# mainboard_valdis.net
KiCad netlist of a schematic drawn in Altium Designer
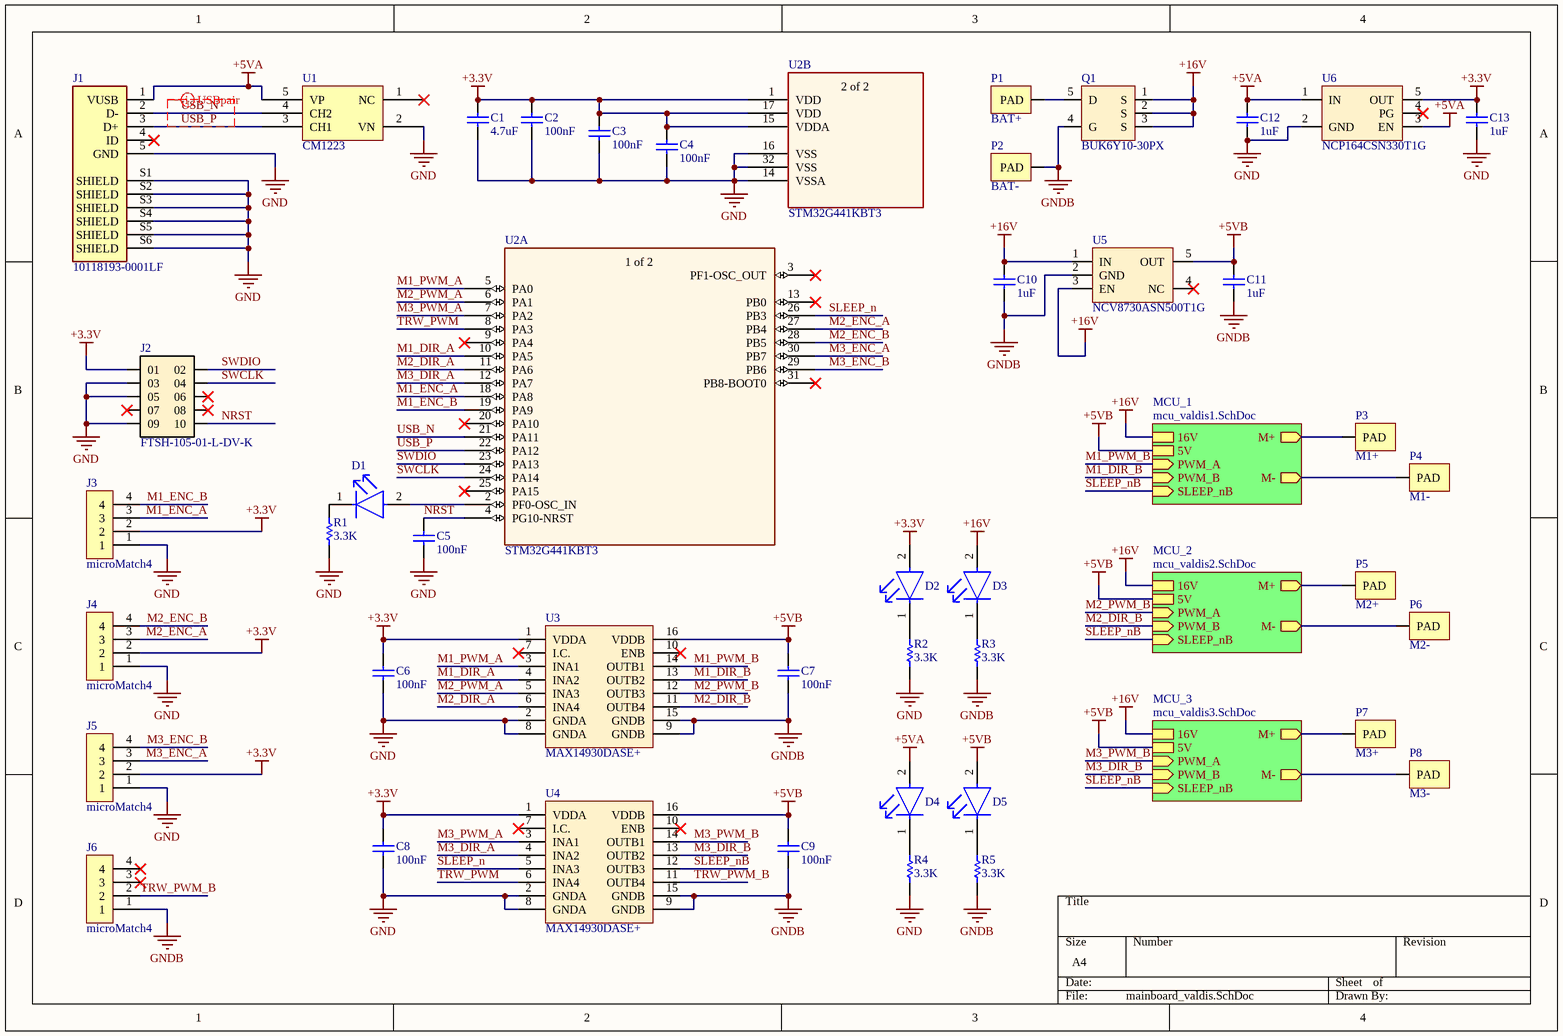
[diagram p0: mainboard_valdis.SchDoc]

(export (version "E")
  (design (tool "Eeschema 10.0.6"))
  (components
    (comp (ref "C1")
      (value "4.7uF")
      (footprint "CAPC1608X90X35ML10T15")
      (description "Chip Capacitor, 22 pF, +/- 5%, 50 V, -55 to 125 degC, 0603 (1608 Metric), RoHS, Tape and Reel")
      (fields (field (name "MANUFACTURER") "Murata"))
      (libsource (lib "Altium Content Vault") (part "CAP-NP-2"))
    )
    (comp (ref "C2")
      (value "100nF")
      (footprint "CAPC1608X90X35ML10T15")
      (description "Chip Capacitor, 22 pF, +/- 5%, 50 V, -55 to 125 degC, 0603 (1608 Metric), RoHS, Tape and Reel")
      (fields (field (name "MANUFACTURER") "Murata"))
      (libsource (lib "Altium Content Vault") (part "CAP-NP-2"))
    )
    (comp (ref "C3")
      (value "100nF")
      (footprint "CAPC1608X90X35ML10T15")
      (description "Chip Capacitor, 22 pF, +/- 5%, 50 V, -55 to 125 degC, 0603 (1608 Metric), RoHS, Tape and Reel")
      (fields (field (name "MANUFACTURER") "Murata"))
      (libsource (lib "Altium Content Vault") (part "CAP-NP-2"))
    )
    (comp (ref "C4")
      (value "100nF")
      (footprint "CAPC1608X90X35ML10T15")
      (description "Chip Capacitor, 22 pF, +/- 5%, 50 V, -55 to 125 degC, 0603 (1608 Metric), RoHS, Tape and Reel")
      (fields (field (name "MANUFACTURER") "Murata"))
      (libsource (lib "Altium Content Vault") (part "CAP-NP-2"))
    )
    (comp (ref "C5")
      (value "100nF")
      (footprint "CAPC1608X90X35ML10T15")
      (description "Chip Capacitor, 22 pF, +/- 5%, 50 V, -55 to 125 degC, 0603 (1608 Metric), RoHS, Tape and Reel")
      (fields (field (name "MANUFACTURER") "Murata"))
      (libsource (lib "Altium Content Vault") (part "CAP-NP-2"))
    )
    (comp (ref "C6")
      (value "100nF")
      (footprint "CAPC1608X90X35ML10T15")
      (description "Chip Capacitor, 22 pF, +/- 5%, 50 V, -55 to 125 degC, 0603 (1608 Metric), RoHS, Tape and Reel")
      (fields (field (name "MANUFACTURER") "Murata"))
      (libsource (lib "Altium Content Vault") (part "CAP-NP-2"))
    )
    (comp (ref "C7")
      (value "100nF")
      (footprint "CAPC1608X90X35ML10T15")
      (description "Chip Capacitor, 22 pF, +/- 5%, 50 V, -55 to 125 degC, 0603 (1608 Metric), RoHS, Tape and Reel")
      (fields (field (name "MANUFACTURER") "Murata"))
      (libsource (lib "Altium Content Vault") (part "CAP-NP-2"))
    )
    (comp (ref "C8")
      (value "100nF")
      (footprint "CAPC1608X90X35ML10T15")
      (description "Chip Capacitor, 22 pF, +/- 5%, 50 V, -55 to 125 degC, 0603 (1608 Metric), RoHS, Tape and Reel")
      (fields (field (name "MANUFACTURER") "Murata"))
      (libsource (lib "Altium Content Vault") (part "CAP-NP-2"))
    )
    (comp (ref "C9")
      (value "100nF")
      (footprint "CAPC1608X90X35ML10T15")
      (description "Chip Capacitor, 22 pF, +/- 5%, 50 V, -55 to 125 degC, 0603 (1608 Metric), RoHS, Tape and Reel")
      (fields (field (name "MANUFACTURER") "Murata"))
      (libsource (lib "Altium Content Vault") (part "CAP-NP-2"))
    )
    (comp (ref "C10")
      (value "1uF")
      (footprint "CAPC1608X90X35ML10T15")
      (description "Chip Capacitor, 22 pF, +/- 5%, 50 V, -55 to 125 degC, 0603 (1608 Metric), RoHS, Tape and Reel")
      (fields (field (name "MANUFACTURER") "Murata"))
      (libsource (lib "Altium Content Vault") (part "CAP-NP-2"))
    )
    (comp (ref "C11")
      (value "1uF")
      (footprint "CAPC1608X90X35ML10T15")
      (description "Chip Capacitor, 22 pF, +/- 5%, 50 V, -55 to 125 degC, 0603 (1608 Metric), RoHS, Tape and Reel")
      (fields (field (name "MANUFACTURER") "Murata"))
      (libsource (lib "Altium Content Vault") (part "CAP-NP-2"))
    )
    (comp (ref "C12")
      (value "1uF")
      (footprint "CAPC1608X90X35ML10T15")
      (description "Chip Capacitor, 22 pF, +/- 5%, 50 V, -55 to 125 degC, 0603 (1608 Metric), RoHS, Tape and Reel")
      (fields (field (name "MANUFACTURER") "Murata"))
      (libsource (lib "Altium Content Vault") (part "CAP-NP-2"))
    )
    (comp (ref "C13")
      (value "1uF")
      (footprint "CAPC1608X90X35ML10T15")
      (description "Chip Capacitor, 22 pF, +/- 5%, 50 V, -55 to 125 degC, 0603 (1608 Metric), RoHS, Tape and Reel")
      (fields (field (name "MANUFACTURER") "Murata"))
      (libsource (lib "Altium Content Vault") (part "CAP-NP-2"))
    )
    (comp (ref "D1")
      (value "LTST-C191TBKT")
      (footprint "FP-LTST-C191TBKT-MFG")
      (description "LED BLUE CLEAR CHIP SMD")
      (libsource (lib "Altium Content Vault") (part "8706943c75ba83719d021d2fdc84c58"))
    )
    (comp (ref "D2")
      (value "LTST-C191TBKT")
      (footprint "FP-LTST-C191TBKT-MFG")
      (description "LED BLUE CLEAR CHIP SMD")
      (libsource (lib "Altium Content Vault") (part "8706943c75ba83719d021d2fdc84c58"))
    )
    (comp (ref "D3")
      (value "LTST-C191TBKT")
      (footprint "FP-LTST-C191TBKT-MFG")
      (description "LED BLUE CLEAR CHIP SMD")
      (libsource (lib "Altium Content Vault") (part "8706943c75ba83719d021d2fdc84c58"))
    )
    (comp (ref "D4")
      (value "LTST-C191TBKT")
      (footprint "FP-LTST-C191TBKT-MFG")
      (description "LED BLUE CLEAR CHIP SMD")
      (libsource (lib "Altium Content Vault") (part "8706943c75ba83719d021d2fdc84c58"))
    )
    (comp (ref "D5")
      (value "LTST-C191TBKT")
      (footprint "FP-LTST-C191TBKT-MFG")
      (description "LED BLUE CLEAR CHIP SMD")
      (libsource (lib "Altium Content Vault") (part "8706943c75ba83719d021d2fdc84c58"))
    )
    (comp (ref "J1")
      (value "10118193-0001LF")
      (footprint "FCI_10118193-0001LF")
      (description "USB - micro B USB 2.0 Receptacle Connector 5 Position Surface Mount, Right Angle; Through Hole")
      (fields (field (name "MF") "Amphenol ICC"))
      (libsource (lib "Valdis_Components") (part "10118193-0001LF"))
    )
    (comp (ref "J2")
      (value "FTSH-105-01-L-DV-K")
      (footprint "FTSH-105-01-XXX-DV-K")
      (libsource (lib "Valdis_Components") (part "FTSH-105-01-L-DV-K"))
    )
    (comp (ref "J3")
      (value "microMatch4")
      (footprint "microMatch4:microMatch4")
      (libsource (lib "Valdis_Components") (part "microMatch4"))
    )
    (comp (ref "J4")
      (value "microMatch4")
      (footprint "microMatch4:microMatch4")
      (libsource (lib "Valdis_Components") (part "microMatch4"))
    )
    (comp (ref "J5")
      (value "microMatch4")
      (footprint "microMatch4:microMatch4")
      (libsource (lib "Valdis_Components") (part "microMatch4"))
    )
    (comp (ref "J6")
      (value "microMatch4")
      (footprint "microMatch4:microMatch4")
      (libsource (lib "Valdis_Components") (part "microMatch4"))
    )
    (comp (ref "P1") (value "BAT+") (footprint "PCBComponent_1") (libsource (lib "") (part "Pad4x4_1")))
    (comp (ref "P2") (value "BAT-") (footprint "PCBComponent_1") (libsource (lib "") (part "Pad4x4_1")))
    (comp (ref "P3")
      (value "M1+")
      (footprint "PCBComponent_1")
      (libsource (lib "Valdis_Components") (part "Pad4x4"))
    )
    (comp (ref "P4")
      (value "M1-")
      (footprint "PCBComponent_1")
      (libsource (lib "Valdis_Components") (part "Pad4x4"))
    )
    (comp (ref "P5")
      (value "M2+")
      (footprint "PCBComponent_1")
      (libsource (lib "Valdis_Components") (part "Pad4x4"))
    )
    (comp (ref "P6")
      (value "M2-")
      (footprint "PCBComponent_1")
      (libsource (lib "Valdis_Components") (part "Pad4x4"))
    )
    (comp (ref "P7")
      (value "M3+")
      (footprint "PCBComponent_1")
      (libsource (lib "Valdis_Components") (part "Pad4x4"))
    )
    (comp (ref "P8")
      (value "M3-")
      (footprint "PCBComponent_1")
      (libsource (lib "Valdis_Components") (part "Pad4x4"))
    )
    (comp (ref "Q1")
      (value "BUK6Y10-30PX")
      (footprint "TO127P600X120-5N")
      (libsource (lib "Valdis_Components") (part "BUK6Y10-30PX"))
    )
    (comp (ref "R1")
      (value "3.3K")
      (footprint "RESC1609X50X30NL8T20")
      (description "Chip Resistor, 0 Ohm, Jumper, 100 mW, -55 to 155 degC, 0603 (1608 Metric), RoHS, Tape and Reel")
      (fields (field (name "MANUFACTURER") "Vishay Semiconductor"))
      (libsource (lib "Altium Content Vault") (part "RES-2"))
    )
    (comp (ref "R2")
      (value "3.3K")
      (footprint "RESC1609X50X30NL8T20")
      (description "Chip Resistor, 0 Ohm, Jumper, 100 mW, -55 to 155 degC, 0603 (1608 Metric), RoHS, Tape and Reel")
      (fields (field (name "MANUFACTURER") "Vishay Semiconductor"))
      (libsource (lib "Altium Content Vault") (part "RES-2"))
    )
    (comp (ref "R3")
      (value "3.3K")
      (footprint "RESC1609X50X30NL8T20")
      (description "Chip Resistor, 0 Ohm, Jumper, 100 mW, -55 to 155 degC, 0603 (1608 Metric), RoHS, Tape and Reel")
      (fields (field (name "MANUFACTURER") "Vishay Semiconductor"))
      (libsource (lib "Altium Content Vault") (part "RES-2"))
    )
    (comp (ref "R4")
      (value "3.3K")
      (footprint "RESC1609X50X30NL8T20")
      (description "Chip Resistor, 0 Ohm, Jumper, 100 mW, -55 to 155 degC, 0603 (1608 Metric), RoHS, Tape and Reel")
      (fields (field (name "MANUFACTURER") "Vishay Semiconductor"))
      (libsource (lib "Altium Content Vault") (part "RES-2"))
    )
    (comp (ref "R5")
      (value "3.3K")
      (footprint "RESC1609X50X30NL8T20")
      (description "Chip Resistor, 0 Ohm, Jumper, 100 mW, -55 to 155 degC, 0603 (1608 Metric), RoHS, Tape and Reel")
      (fields (field (name "MANUFACTURER") "Vishay Semiconductor"))
      (libsource (lib "Altium Content Vault") (part "RES-2"))
    )
    (comp (ref "U1")
      (value "CM1223")
      (footprint "SOT23-5")
      (libsource (lib "Valdis_Components") (part "CM1223"))
    )
    (comp (ref "U2")
      (value "STM32G441KBT3")
      (footprint "LQFP32_7X7_STM")
      (description "No Description Available")
      (fields (field (name "COPYRIGHT") "Copyright (C) 2018 Accelerated Designs. All rights reserved"))
      (libsource (lib "Valdis_Components") (part "STM32G441KBT3"))
    )
    (comp (ref "U3")
      (value "MAX14930DASE+")
      (footprint "21-0041_S16+1_MXM")
      (libsource (lib "Valdis_Components") (part "MAX14930DASE+"))
    )
    (comp (ref "U4")
      (value "MAX14930DASE+")
      (footprint "21-0041_S16+1_MXM")
      (libsource (lib "Valdis_Components") (part "MAX14930DASE+"))
    )
    (comp (ref "U5")
      (value "NCV8730ASN500T1G")
      (footprint "NCV8730:TSSOP5")
      (libsource (lib "NCV8730ASN500T1G") (part "NCV8730ASN500T1G"))
    )
    (comp (ref "U6")
      (value "NCP164CSN330T1G")
      (footprint "SOP95P275X110-5N")
      (libsource (lib "Valdis_Components") (part "NCP164CSN330T1G"))
    )
  )
  (nets
    (net (code "1") (name "+3.3V") (class "Default")
      (node (ref "C1") (pin "2") (pinfunction "2_2") (pintype "passive"))
      (node (ref "C13") (pin "2") (pinfunction "2_2") (pintype "passive"))
      (node (ref "C2") (pin "2") (pinfunction "2_2") (pintype "passive"))
      (node (ref "C3") (pin "2") (pinfunction "2_2") (pintype "passive"))
      (node (ref "C4") (pin "2") (pinfunction "2_2") (pintype "passive"))
      (node (ref "C6") (pin "2") (pinfunction "2_2") (pintype "passive"))
      (node (ref "C8") (pin "2") (pinfunction "2_2") (pintype "passive"))
      (node (ref "D2") (pin "2") (pinfunction "A_2") (pintype "passive"))
      (node (ref "J2") (pin "1") (pinfunction "01_1") (pintype "passive"))
      (node (ref "J3") (pin "2") (pinfunction "2_2") (pintype "passive"))
      (node (ref "J4") (pin "2") (pinfunction "2_2") (pintype "passive"))
      (node (ref "J5") (pin "2") (pinfunction "2_2") (pintype "passive"))
      (node (ref "U2") (pin "1") (pinfunction "VDD_1") (pintype "power_in"))
      (node (ref "U2") (pin "15") (pinfunction "VDDA_15") (pintype "power_in"))
      (node (ref "U2") (pin "17") (pinfunction "VDD_17") (pintype "power_in"))
      (node (ref "U3") (pin "1") (pinfunction "VDDA_1") (pintype "passive"))
      (node (ref "U4") (pin "1") (pinfunction "VDDA_1") (pintype "passive"))
      (node (ref "U6") (pin "5") (pinfunction "OUT_5") (pintype "passive"))
    )
    (net (code "2") (name "+5VA") (class "Default")
      (node (ref "C12") (pin "2") (pinfunction "2_2") (pintype "passive"))
      (node (ref "D4") (pin "2") (pinfunction "A_2") (pintype "passive"))
      (node (ref "J1") (pin "1") (pinfunction "VUSB_1") (pintype "passive"))
      (node (ref "U1") (pin "5") (pinfunction "VP_5") (pintype "passive"))
      (node (ref "U6") (pin "1") (pinfunction "IN_1") (pintype "passive"))
      (node (ref "U6") (pin "3") (pinfunction "EN_3") (pintype "passive"))
    )
    (net (code "3") (name "+5VB") (class "Default")
      (node (ref "C11") (pin "2") (pinfunction "2_2") (pintype "passive"))
      (node (ref "C7") (pin "2") (pinfunction "2_2") (pintype "passive"))
      (node (ref "C9") (pin "2") (pinfunction "2_2") (pintype "passive"))
      (node (ref "D5") (pin "2") (pinfunction "A_2") (pintype "passive"))
      (node (ref "U3") (pin "16") (pinfunction "VDDB_16") (pintype "passive"))
      (node (ref "U4") (pin "16") (pinfunction "VDDB_16") (pintype "passive"))
      (node (ref "U5") (pin "5") (pinfunction "OUT_5") (pintype "passive"))
    )
    (net (code "4") (name "+16V") (class "Default")
      (node (ref "C10") (pin "2") (pinfunction "2_2") (pintype "passive"))
      (node (ref "D3") (pin "2") (pinfunction "A_2") (pintype "passive"))
      (node (ref "Q1") (pin "1") (pinfunction "S_1") (pintype "passive"))
      (node (ref "Q1") (pin "2") (pinfunction "S_2") (pintype "passive"))
      (node (ref "Q1") (pin "3") (pinfunction "S_3") (pintype "passive"))
      (node (ref "U5") (pin "1") (pinfunction "IN_1") (pintype "passive"))
      (node (ref "U5") (pin "3") (pinfunction "EN_3") (pintype "passive"))
    )
    (net (code "5") (name "/M+") (class "Default")
      (node (ref "P7") (pin "1") (pinfunction "PAD_1") (pintype "passive"))
    )
    (net (code "6") (name "/M+_1") (class "Default")
      (node (ref "P3") (pin "1") (pinfunction "PAD_1") (pintype "passive"))
    )
    (net (code "7") (name "/M+_2") (class "Default")
      (node (ref "P5") (pin "1") (pinfunction "PAD_1") (pintype "passive"))
    )
    (net (code "8") (name "/M-") (class "Default")
      (node (ref "P8") (pin "1") (pinfunction "PAD_1") (pintype "passive"))
    )
    (net (code "9") (name "/M-_1") (class "Default")
      (node (ref "P4") (pin "1") (pinfunction "PAD_1") (pintype "passive"))
    )
    (net (code "10") (name "/M-_2") (class "Default")
      (node (ref "P6") (pin "1") (pinfunction "PAD_1") (pintype "passive"))
    )
    (net (code "11") (name "/M1_DIR_A") (class "Default")
      (node (ref "U2") (pin "10") (pinfunction "PA5_10") (pintype "bidirectional"))
      (node (ref "U3") (pin "4") (pinfunction "INA2_4") (pintype "passive"))
    )
    (net (code "12") (name "/M1_DIR_B") (class "Default")
      (node (ref "U3") (pin "13") (pinfunction "OUTB2_13") (pintype "passive"))
    )
    (net (code "13") (name "/M1_ENC_A") (class "Default")
      (node (ref "J3") (pin "3") (pinfunction "3_3") (pintype "passive"))
      (node (ref "U2") (pin "18") (pinfunction "PA8_18") (pintype "bidirectional"))
    )
    (net (code "14") (name "/M1_ENC_B") (class "Default")
      (node (ref "J3") (pin "4") (pinfunction "4_4") (pintype "passive"))
      (node (ref "U2") (pin "19") (pinfunction "PA9_19") (pintype "bidirectional"))
    )
    (net (code "15") (name "/M1_PWM_A") (class "Default")
      (node (ref "U2") (pin "5") (pinfunction "PA0_5") (pintype "bidirectional"))
      (node (ref "U3") (pin "3") (pinfunction "INA1_3") (pintype "passive"))
    )
    (net (code "16") (name "/M1_PWM_B") (class "Default")
      (node (ref "U3") (pin "14") (pinfunction "OUTB1_14") (pintype "passive"))
    )
    (net (code "17") (name "/M2_DIR_A") (class "Default")
      (node (ref "U2") (pin "11") (pinfunction "PA6_11") (pintype "bidirectional"))
      (node (ref "U3") (pin "6") (pinfunction "INA4_6") (pintype "passive"))
    )
    (net (code "18") (name "/M2_DIR_B") (class "Default")
      (node (ref "U3") (pin "11") (pinfunction "OUTB4_11") (pintype "passive"))
    )
    (net (code "19") (name "/M2_ENC_A") (class "Default")
      (node (ref "J4") (pin "3") (pinfunction "3_3") (pintype "passive"))
      (node (ref "U2") (pin "27") (pinfunction "PB4_27") (pintype "bidirectional"))
    )
    (net (code "20") (name "/M2_ENC_B") (class "Default")
      (node (ref "J4") (pin "4") (pinfunction "4_4") (pintype "passive"))
      (node (ref "U2") (pin "28") (pinfunction "PB5_28") (pintype "bidirectional"))
    )
    (net (code "21") (name "/M2_PWM_A") (class "Default")
      (node (ref "U2") (pin "6") (pinfunction "PA1_6") (pintype "bidirectional"))
      (node (ref "U3") (pin "5") (pinfunction "INA3_5") (pintype "passive"))
    )
    (net (code "22") (name "/M2_PWM_B") (class "Default")
      (node (ref "U3") (pin "12") (pinfunction "OUTB3_12") (pintype "passive"))
    )
    (net (code "23") (name "/M3_DIR_A") (class "Default")
      (node (ref "U2") (pin "12") (pinfunction "PA7_12") (pintype "bidirectional"))
      (node (ref "U4") (pin "4") (pinfunction "INA2_4") (pintype "passive"))
    )
    (net (code "24") (name "/M3_DIR_B") (class "Default")
      (node (ref "U4") (pin "13") (pinfunction "OUTB2_13") (pintype "passive"))
    )
    (net (code "25") (name "/M3_ENC_A") (class "Default")
      (node (ref "J5") (pin "3") (pinfunction "3_3") (pintype "passive"))
      (node (ref "U2") (pin "30") (pinfunction "PB7_30") (pintype "bidirectional"))
    )
    (net (code "26") (name "/M3_ENC_B") (class "Default")
      (node (ref "J5") (pin "4") (pinfunction "4_4") (pintype "passive"))
      (node (ref "U2") (pin "29") (pinfunction "PB6_29") (pintype "bidirectional"))
    )
    (net (code "27") (name "/M3_PWM_A") (class "Default")
      (node (ref "U2") (pin "7") (pinfunction "PA2_7") (pintype "bidirectional"))
      (node (ref "U4") (pin "3") (pinfunction "INA1_3") (pintype "passive"))
    )
    (net (code "28") (name "/M3_PWM_B") (class "Default")
      (node (ref "U4") (pin "14") (pinfunction "OUTB1_14") (pintype "passive"))
    )
    (net (code "29") (name "/NRST") (class "Default")
      (node (ref "C5") (pin "2") (pinfunction "2_2") (pintype "passive"))
      (node (ref "J2") (pin "10") (pinfunction "10_10") (pintype "passive"))
      (node (ref "U2") (pin "4") (pinfunction "PG10-NRST_4") (pintype "bidirectional"))
    )
    (net (code "30") (name "/SLEEP_n") (class "Default")
      (node (ref "U2") (pin "26") (pinfunction "PB3_26") (pintype "bidirectional"))
      (node (ref "U4") (pin "5") (pinfunction "INA3_5") (pintype "passive"))
    )
    (net (code "31") (name "/SLEEP_nB") (class "Default")
      (node (ref "U4") (pin "12") (pinfunction "OUTB3_12") (pintype "passive"))
    )
    (net (code "32") (name "/SWCLK") (class "Default")
      (node (ref "J2") (pin "4") (pinfunction "04_4") (pintype "passive"))
      (node (ref "U2") (pin "24") (pinfunction "PA14_24") (pintype "bidirectional"))
    )
    (net (code "33") (name "/SWDIO") (class "Default")
      (node (ref "J2") (pin "2") (pinfunction "02_2") (pintype "passive"))
      (node (ref "U2") (pin "23") (pinfunction "PA13_23") (pintype "bidirectional"))
    )
    (net (code "34") (name "/TRW_PWM") (class "Default")
      (node (ref "U2") (pin "8") (pinfunction "PA3_8") (pintype "bidirectional"))
      (node (ref "U4") (pin "6") (pinfunction "INA4_6") (pintype "passive"))
    )
    (net (code "35") (name "/TRW_PWM_B") (class "Default")
      (node (ref "J6") (pin "2") (pinfunction "2_2") (pintype "passive"))
      (node (ref "U4") (pin "11") (pinfunction "OUTB4_11") (pintype "passive"))
    )
    (net (code "36") (name "/USB_N") (class "Default")
      (node (ref "J1") (pin "2") (pinfunction "D-_2") (pintype "passive"))
      (node (ref "U1") (pin "4") (pinfunction "CH2_4") (pintype "passive"))
      (node (ref "U2") (pin "21") (pinfunction "PA11_21") (pintype "bidirectional"))
    )
    (net (code "37") (name "/USB_P") (class "Default")
      (node (ref "J1") (pin "3") (pinfunction "D+_3") (pintype "passive"))
      (node (ref "U1") (pin "3") (pinfunction "CH1_3") (pintype "passive"))
      (node (ref "U2") (pin "22") (pinfunction "PA12_22") (pintype "bidirectional"))
    )
    (net (code "38") (name "GND") (class "Default")
      (node (ref "C1") (pin "1") (pinfunction "1_1") (pintype "passive"))
      (node (ref "C12") (pin "1") (pinfunction "1_1") (pintype "passive"))
      (node (ref "C13") (pin "1") (pinfunction "1_1") (pintype "passive"))
      (node (ref "C2") (pin "1") (pinfunction "1_1") (pintype "passive"))
      (node (ref "C3") (pin "1") (pinfunction "1_1") (pintype "passive"))
      (node (ref "C4") (pin "1") (pinfunction "1_1") (pintype "passive"))
      (node (ref "C5") (pin "1") (pinfunction "1_1") (pintype "passive"))
      (node (ref "C6") (pin "1") (pinfunction "1_1") (pintype "passive"))
      (node (ref "C8") (pin "1") (pinfunction "1_1") (pintype "passive"))
      (node (ref "J1") (pin "5") (pinfunction "GND_5") (pintype "passive"))
      (node (ref "J1") (pin "S1") (pinfunction "SHIELD_S1") (pintype "passive"))
      (node (ref "J1") (pin "S2") (pinfunction "SHIELD_S2") (pintype "passive"))
      (node (ref "J1") (pin "S3") (pinfunction "SHIELD_S3") (pintype "passive"))
      (node (ref "J1") (pin "S4") (pinfunction "SHIELD_S4") (pintype "passive"))
      (node (ref "J1") (pin "S5") (pinfunction "SHIELD_S5") (pintype "passive"))
      (node (ref "J1") (pin "S6") (pinfunction "SHIELD_S6") (pintype "passive"))
      (node (ref "J2") (pin "3") (pinfunction "03_3") (pintype "passive"))
      (node (ref "J2") (pin "5") (pinfunction "05_5") (pintype "passive"))
      (node (ref "J2") (pin "9") (pinfunction "09_9") (pintype "passive"))
      (node (ref "J3") (pin "1") (pinfunction "1_1") (pintype "passive"))
      (node (ref "J4") (pin "1") (pinfunction "1_1") (pintype "passive"))
      (node (ref "J5") (pin "1") (pinfunction "1_1") (pintype "passive"))
      (node (ref "R1") (pin "1") (pinfunction "1_1") (pintype "passive"))
      (node (ref "R2") (pin "1") (pinfunction "1_1") (pintype "passive"))
      (node (ref "R4") (pin "1") (pinfunction "1_1") (pintype "passive"))
      (node (ref "U1") (pin "2") (pinfunction "VN_2") (pintype "passive"))
      (node (ref "U2") (pin "14") (pinfunction "VSSA_14") (pintype "passive"))
      (node (ref "U2") (pin "16") (pinfunction "VSS_16") (pintype "passive"))
      (node (ref "U2") (pin "32") (pinfunction "VSS_32") (pintype "passive"))
      (node (ref "U3") (pin "2") (pinfunction "GNDA_2") (pintype "passive"))
      (node (ref "U3") (pin "8") (pinfunction "GNDA_8") (pintype "passive"))
      (node (ref "U4") (pin "2") (pinfunction "GNDA_2") (pintype "passive"))
      (node (ref "U4") (pin "8") (pinfunction "GNDA_8") (pintype "passive"))
      (node (ref "U6") (pin "2") (pinfunction "GND_2") (pintype "passive"))
    )
    (net (code "39") (name "GNDB") (class "Default")
      (node (ref "C10") (pin "1") (pinfunction "1_1") (pintype "passive"))
      (node (ref "C11") (pin "1") (pinfunction "1_1") (pintype "passive"))
      (node (ref "C7") (pin "1") (pinfunction "1_1") (pintype "passive"))
      (node (ref "C9") (pin "1") (pinfunction "1_1") (pintype "passive"))
      (node (ref "J6") (pin "1") (pinfunction "1_1") (pintype "passive"))
      (node (ref "P2") (pin "1") (pinfunction "PAD_1") (pintype "passive"))
      (node (ref "Q1") (pin "4") (pinfunction "G_4") (pintype "passive"))
      (node (ref "R3") (pin "1") (pinfunction "1_1") (pintype "passive"))
      (node (ref "R5") (pin "1") (pinfunction "1_1") (pintype "passive"))
      (node (ref "U3") (pin "15") (pinfunction "GNDB_15") (pintype "passive"))
      (node (ref "U3") (pin "9") (pinfunction "GNDB_9") (pintype "passive"))
      (node (ref "U4") (pin "15") (pinfunction "GNDB_15") (pintype "passive"))
      (node (ref "U4") (pin "9") (pinfunction "GNDB_9") (pintype "passive"))
      (node (ref "U5") (pin "2") (pinfunction "GND_2") (pintype "passive"))
    )
    (net (code "40") (name "Net-(D1-A)") (class "Default")
      (node (ref "D1") (pin "2") (pinfunction "A_2") (pintype "passive"))
      (node (ref "U2") (pin "2") (pinfunction "PF0-OSC_IN_2") (pintype "bidirectional"))
    )
    (net (code "41") (name "Net-(D1-C)") (class "Default")
      (node (ref "D1") (pin "1") (pinfunction "C_1") (pintype "passive"))
      (node (ref "R1") (pin "2") (pinfunction "2_2") (pintype "passive"))
    )
    (net (code "42") (name "Net-(D2-C)") (class "Default")
      (node (ref "D2") (pin "1") (pinfunction "C_1") (pintype "passive"))
      (node (ref "R2") (pin "2") (pinfunction "2_2") (pintype "passive"))
    )
    (net (code "43") (name "Net-(D3-C)") (class "Default")
      (node (ref "D3") (pin "1") (pinfunction "C_1") (pintype "passive"))
      (node (ref "R3") (pin "2") (pinfunction "2_2") (pintype "passive"))
    )
    (net (code "44") (name "Net-(D4-C)") (class "Default")
      (node (ref "D4") (pin "1") (pinfunction "C_1") (pintype "passive"))
      (node (ref "R4") (pin "2") (pinfunction "2_2") (pintype "passive"))
    )
    (net (code "45") (name "Net-(D5-C)") (class "Default")
      (node (ref "D5") (pin "1") (pinfunction "C_1") (pintype "passive"))
      (node (ref "R5") (pin "2") (pinfunction "2_2") (pintype "passive"))
    )
    (net (code "46") (name "Net-(P1-PAD)") (class "Default")
      (node (ref "P1") (pin "1") (pinfunction "PAD_1") (pintype "passive"))
      (node (ref "Q1") (pin "5") (pinfunction "D_5") (pintype "passive"))
    )
    (net (code "47") (name "unconnected-(J1-ID-Pad4)") (class "Default")
      (node (ref "J1") (pin "4") (pinfunction "ID_4") (pintype "passive+no_connect"))
    )
    (net (code "48") (name "unconnected-(J2-06-Pad6)") (class "Default")
      (node (ref "J2") (pin "6") (pinfunction "06_6") (pintype "passive+no_connect"))
    )
    (net (code "49") (name "unconnected-(J2-07-Pad7)") (class "Default")
      (node (ref "J2") (pin "7") (pinfunction "07_7") (pintype "passive+no_connect"))
    )
    (net (code "50") (name "unconnected-(J2-08-Pad8)") (class "Default")
      (node (ref "J2") (pin "8") (pinfunction "08_8") (pintype "passive+no_connect"))
    )
    (net (code "51") (name "unconnected-(J6-Pad3)") (class "Default")
      (node (ref "J6") (pin "3") (pinfunction "3_3") (pintype "passive+no_connect"))
    )
    (net (code "52") (name "unconnected-(J6-Pad4)") (class "Default")
      (node (ref "J6") (pin "4") (pinfunction "4_4") (pintype "passive+no_connect"))
    )
    (net (code "53") (name "unconnected-(U1-NC-Pad1)") (class "Default")
      (node (ref "U1") (pin "1") (pinfunction "NC_1") (pintype "passive+no_connect"))
    )
    (net (code "54") (name "unconnected-(U2A-PA4-Pad9)") (class "Default")
      (node (ref "U2") (pin "9") (pinfunction "PA4_9") (pintype "bidirectional+no_connect"))
    )
    (net (code "55") (name "unconnected-(U2A-PA10-Pad20)") (class "Default")
      (node (ref "U2") (pin "20") (pinfunction "PA10_20") (pintype "bidirectional+no_connect"))
    )
    (net (code "56") (name "unconnected-(U2A-PA15-Pad25)") (class "Default")
      (node (ref "U2") (pin "25") (pinfunction "PA15_25") (pintype "bidirectional+no_connect"))
    )
    (net (code "57") (name "unconnected-(U2A-PB0-Pad13)") (class "Default")
      (node (ref "U2") (pin "13") (pinfunction "PB0_13") (pintype "bidirectional+no_connect"))
    )
    (net (code "58") (name "unconnected-(U2A-PB8-BOOT0-Pad31)") (class "Default")
      (node (ref "U2") (pin "31") (pinfunction "PB8-BOOT0_31") (pintype "bidirectional+no_connect"))
    )
    (net (code "59") (name "unconnected-(U2A-PF1-OSC_OUT-Pad3)") (class "Default")
      (node (ref "U2") (pin "3") (pinfunction "PF1-OSC_OUT_3") (pintype "bidirectional+no_connect"))
    )
    (net (code "60") (name "unconnected-(U3-ENB-Pad10)") (class "Default")
      (node (ref "U3") (pin "10") (pinfunction "ENB_10") (pintype "passive+no_connect"))
    )
    (net (code "61") (name "unconnected-(U3-I.C.-Pad7)") (class "Default")
      (node (ref "U3") (pin "7") (pinfunction "I.C._7") (pintype "passive+no_connect"))
    )
    (net (code "62") (name "unconnected-(U4-ENB-Pad10)") (class "Default")
      (node (ref "U4") (pin "10") (pinfunction "ENB_10") (pintype "passive+no_connect"))
    )
    (net (code "63") (name "unconnected-(U4-I.C.-Pad7)") (class "Default")
      (node (ref "U4") (pin "7") (pinfunction "I.C._7") (pintype "passive+no_connect"))
    )
    (net (code "64") (name "unconnected-(U5-NC-Pad4)") (class "Default")
      (node (ref "U5") (pin "4") (pinfunction "NC_4") (pintype "passive+no_connect"))
    )
    (net (code "65") (name "unconnected-(U6-PG-Pad4)") (class "Default")
      (node (ref "U6") (pin "4") (pinfunction "PG_4") (pintype "passive+no_connect"))
    )
  )
)
